# LVDS_IFC_DAC.net
KiCad netlist of a schematic drawn in Altium Designer
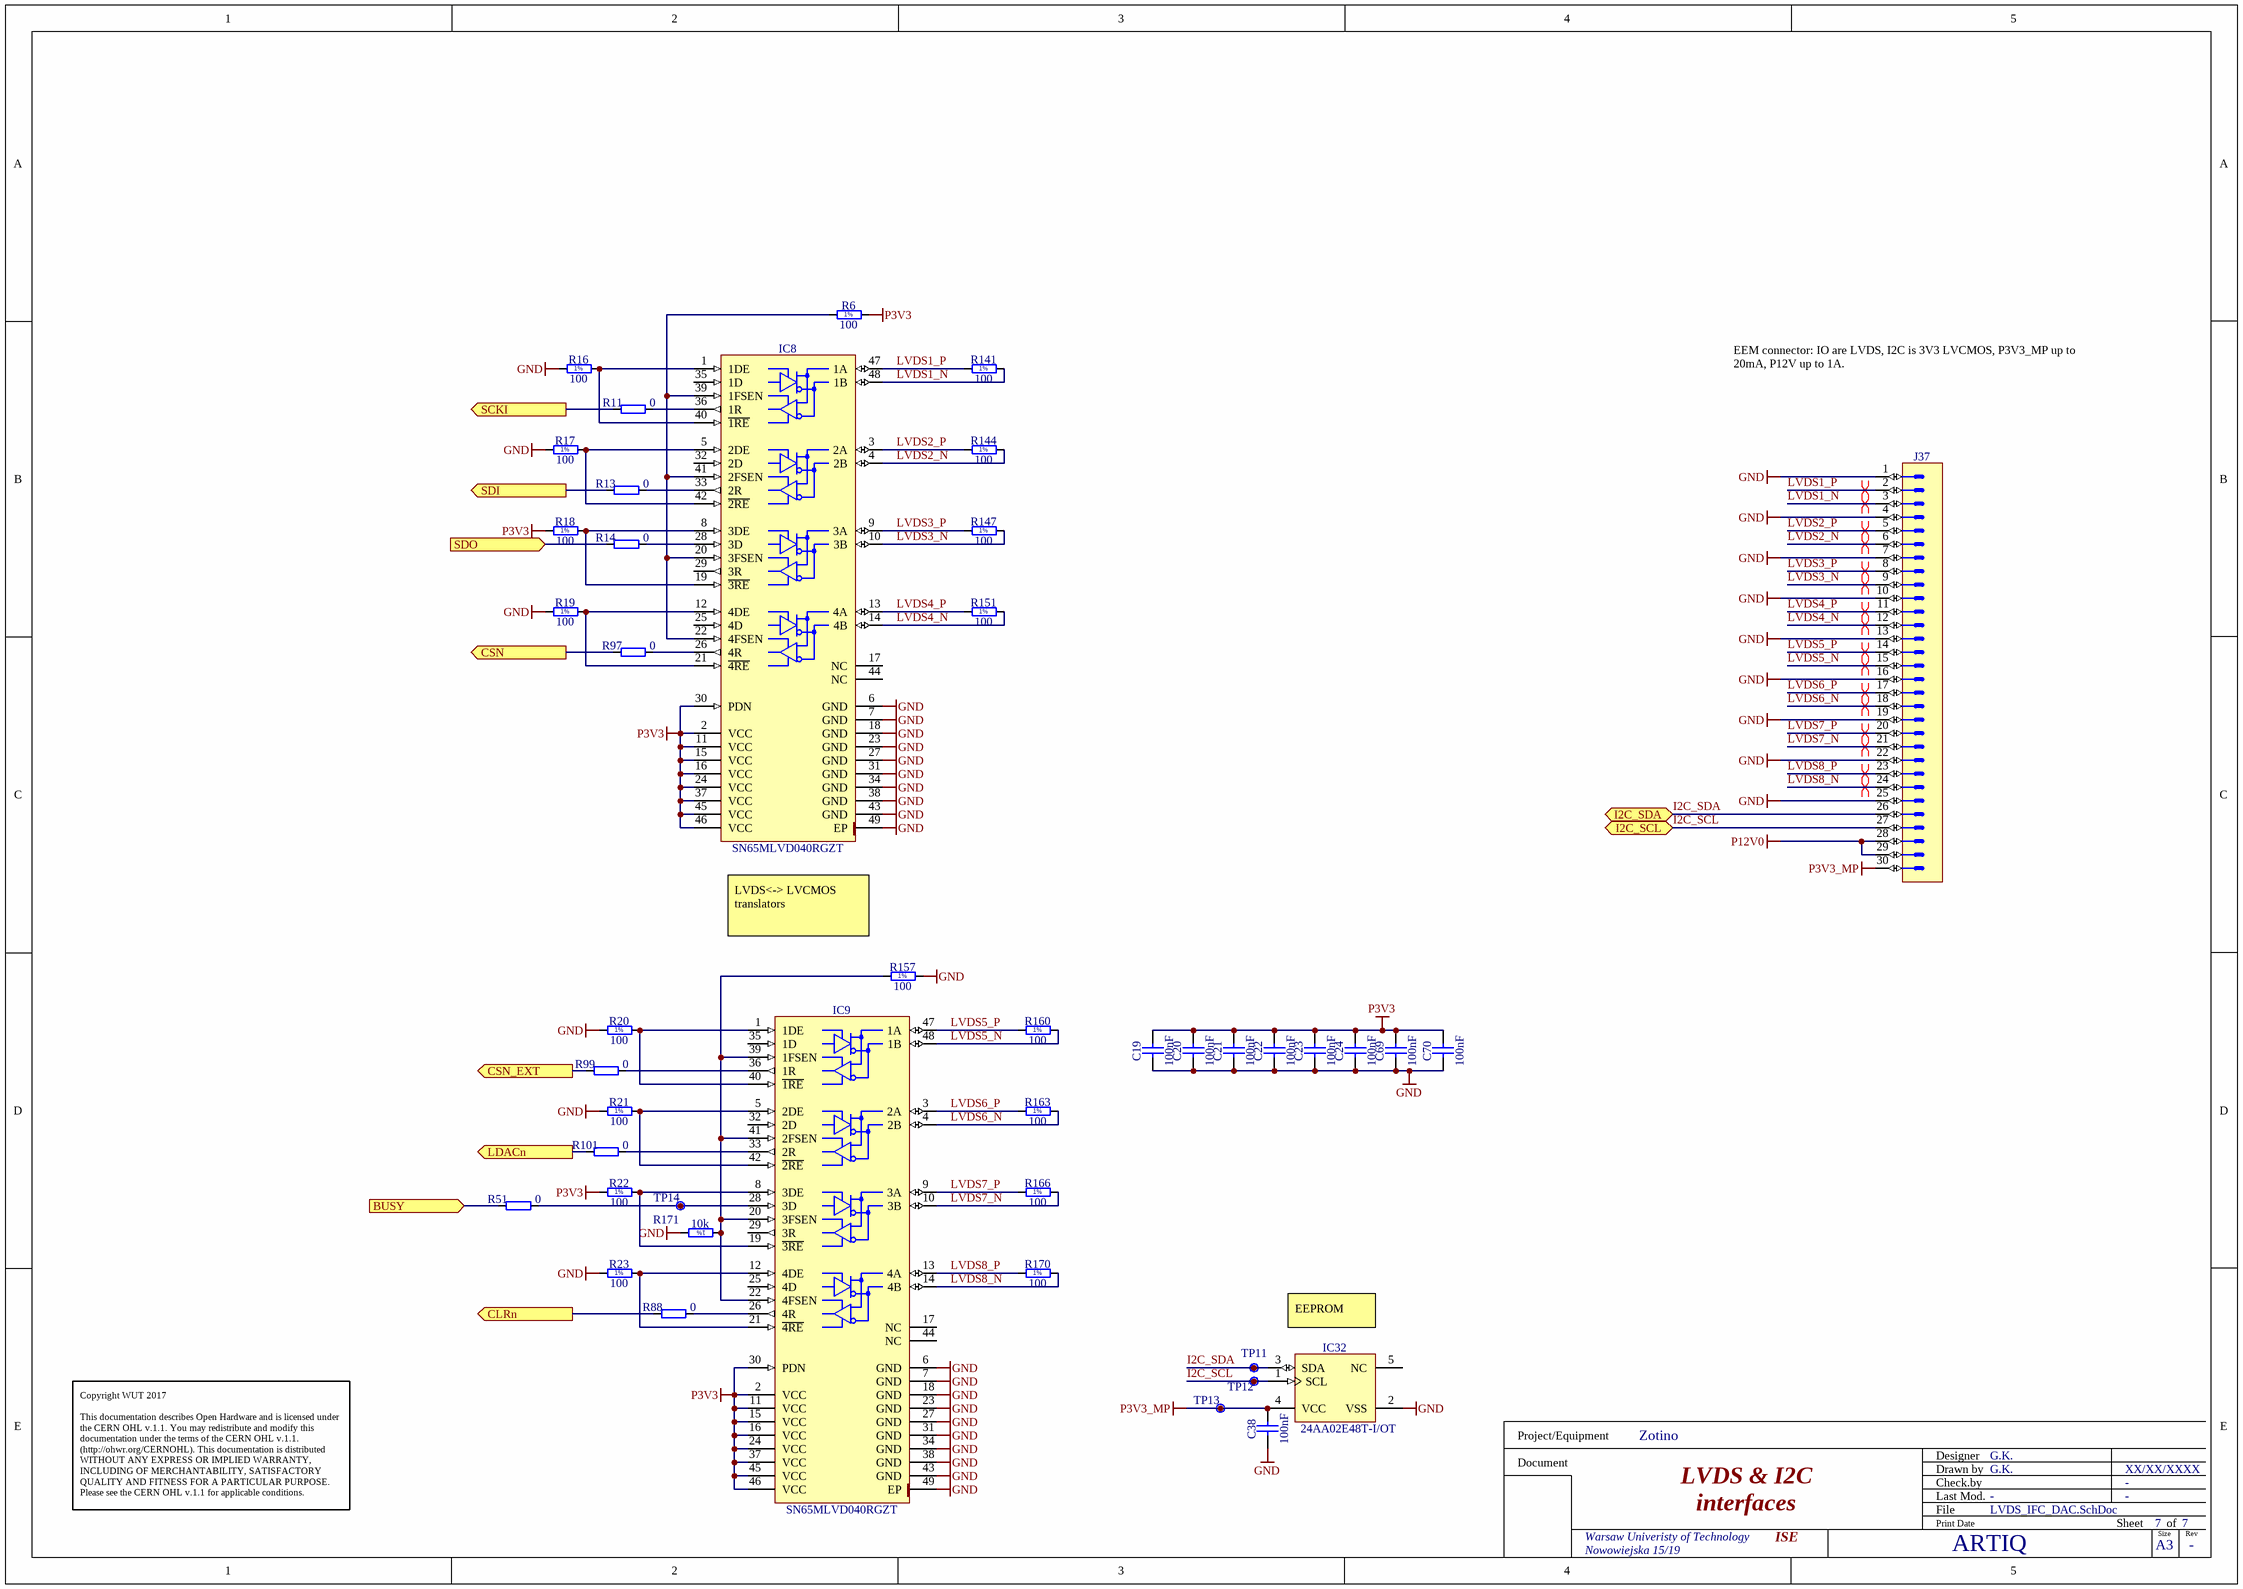
[diagram p0: LVDS_IFC_DAC.SchDoc]

(export (version "E")
  (design (tool "Eeschema 10.0.6"))
  (components
    (comp (ref "C19")
      (value "100nF")
      (footprint "CAPC1005X55N")
      (description "Non-polarised capacitor")
      (fields
        (field (name "PART NUMBER") "CC0402_100NF_16V_10%_X5R")
        (field (name "VOLTAGE") "16V")
        (field (name "AUTHOR") "CERN DEM JLC")
      )
      (libsource (lib "Capacitors") (part "Capacitor - non polarized"))
    )
    (comp (ref "C20")
      (value "100nF")
      (footprint "CAPC1005X55N")
      (description "Non-polarised capacitor")
      (fields
        (field (name "PART NUMBER") "CC0402_100NF_16V_10%_X5R")
        (field (name "VOLTAGE") "16V")
        (field (name "AUTHOR") "CERN DEM JLC")
      )
      (libsource (lib "Capacitors") (part "Capacitor - non polarized"))
    )
    (comp (ref "C21")
      (value "100nF")
      (footprint "CAPC1005X55N")
      (description "Non-polarised capacitor")
      (fields
        (field (name "PART NUMBER") "CC0402_100NF_16V_10%_X5R")
        (field (name "VOLTAGE") "16V")
        (field (name "AUTHOR") "CERN DEM JLC")
      )
      (libsource (lib "Capacitors") (part "Capacitor - non polarized"))
    )
    (comp (ref "C22")
      (value "100nF")
      (footprint "CAPC1005X55N")
      (description "Non-polarised capacitor")
      (fields
        (field (name "PART NUMBER") "CC0402_100NF_16V_10%_X5R")
        (field (name "VOLTAGE") "16V")
        (field (name "AUTHOR") "CERN DEM JLC")
      )
      (libsource (lib "Capacitors") (part "Capacitor - non polarized"))
    )
    (comp (ref "C23")
      (value "100nF")
      (footprint "CAPC1005X55N")
      (description "Non-polarised capacitor")
      (fields
        (field (name "PART NUMBER") "CC0402_100NF_16V_10%_X5R")
        (field (name "VOLTAGE") "16V")
        (field (name "AUTHOR") "CERN DEM JLC")
      )
      (libsource (lib "Capacitors") (part "Capacitor - non polarized"))
    )
    (comp (ref "C24")
      (value "100nF")
      (footprint "CAPC1005X55N")
      (description "Non-polarised capacitor")
      (fields
        (field (name "PART NUMBER") "CC0402_100NF_16V_10%_X5R")
        (field (name "VOLTAGE") "16V")
        (field (name "AUTHOR") "CERN DEM JLC")
      )
      (libsource (lib "Capacitors") (part "Capacitor - non polarized"))
    )
    (comp (ref "C38")
      (value "100nF")
      (footprint "CAPC1005X55N")
      (description "Non-polarised capacitor")
      (fields
        (field (name "PART NUMBER") "CC0402_100NF_16V_10%_X5R")
        (field (name "VOLTAGE") "16V")
        (field (name "AUTHOR") "CERN DEM JLC")
      )
      (libsource (lib "Capacitors") (part "Capacitor - non polarized"))
    )
    (comp (ref "C69")
      (value "100nF")
      (footprint "CAPC1005X55N")
      (description "Non-polarised capacitor")
      (fields
        (field (name "PART NUMBER") "CC0402_100NF_16V_10%_X5R")
        (field (name "VOLTAGE") "16V")
        (field (name "AUTHOR") "CERN DEM JLC")
      )
      (libsource (lib "Capacitors") (part "Capacitor - non polarized"))
    )
    (comp (ref "C70")
      (value "100nF")
      (footprint "CAPC1005X55N")
      (description "Non-polarised capacitor")
      (fields
        (field (name "PART NUMBER") "CC0402_100NF_16V_10%_X5R")
        (field (name "VOLTAGE") "16V")
        (field (name "AUTHOR") "CERN DEM JLC")
      )
      (libsource (lib "Capacitors") (part "Capacitor - non polarized"))
    )
    (comp (ref "IC8")
      (value "SN65MLVD040RGZT")
      (footprint "QFN50P700X700X100-49N-S420")
      (description "4-Channel Half-Duplex M-LVDS Line Transceiver")
      (fields (field (name "MANUFACTURER") "TEXAS INSTRUMENTS") (field (name "AUTHOR") "CERN DEM JLC"))
      (libsource (lib "ICs And Semiconductors") (part "SN65MLVD040"))
    )
    (comp (ref "IC9")
      (value "SN65MLVD040RGZT")
      (footprint "QFN50P700X700X100-49N-S420")
      (description "4-Channel Half-Duplex M-LVDS Line Transceiver")
      (fields (field (name "MANUFACTURER") "TEXAS INSTRUMENTS") (field (name "AUTHOR") "CERN DEM JLC"))
      (libsource (lib "ICs And Semiconductors") (part "SN65MLVD040"))
    )
    (comp (ref "IC32")
      (value "24AA02E48T-I/OT")
      (footprint "SOT95P280X145-5N")
      (description "1.7V-5.5V, 2K I2C Serial EEPROM With EUI-48 Node Identity")
      (fields (field (name "MANUFACTURER") "MICROCHIP TECHNOLOGY") (field (name "AUTHOR") "CERN DEM MR"))
      (libsource (lib "ICs And Semiconductors") (part "24AA02E48T-I/OT"))
    )
    (comp (ref "J37")
      (value "~")
      (footprint "3M_N2530-6002RB")
      (description "Connector 30 Male")
      (fields
        (field (name "PART NUMBER") "3M_N2530-6002RB")
        (field (name "MANUFACTURER") "3M")
        (field (name "AUTHOR") "CERN DEM JLC")
      )
      (libsource (lib "Connectors") (part "Connector 30 Male"))
    )
    (comp (ref "R6")
      (value "100")
      (footprint "RESC1005X40N")
      (description "Resistor - 1%")
      (fields
        (field (name "PART NUMBER") "R0402_100R_1%_0.1W_100PPM")
        (field (name "POWER") "0.1W")
        (field (name "AUTHOR") "CERN DEM JLC")
      )
      (libsource (lib "Resistors") (part "Resistor - 1%"))
    )
    (comp (ref "R11")
      (value "0")
      (footprint "RESC1005X40N")
      (description "Resistor")
      (fields
        (field (name "PART NUMBER") "R0402_0R_JUMPER")
        (field (name "MANUFACTURER") "GENERIC")
        (field (name "AUTHOR") "CERN DEM JLC")
      )
      (libsource (lib "Resistors") (part "Resistor"))
    )
    (comp (ref "R13")
      (value "0")
      (footprint "RESC1005X40N")
      (description "Resistor")
      (fields
        (field (name "PART NUMBER") "R0402_0R_JUMPER")
        (field (name "MANUFACTURER") "GENERIC")
        (field (name "AUTHOR") "CERN DEM JLC")
      )
      (libsource (lib "Resistors") (part "Resistor"))
    )
    (comp (ref "R14")
      (value "0")
      (footprint "RESC1005X40N")
      (description "Resistor")
      (fields
        (field (name "PART NUMBER") "R0402_0R_JUMPER")
        (field (name "MANUFACTURER") "GENERIC")
        (field (name "AUTHOR") "CERN DEM JLC")
      )
      (libsource (lib "Resistors") (part "Resistor"))
    )
    (comp (ref "R16")
      (value "100")
      (footprint "RESC1005X40N")
      (description "Resistor - 1%")
      (fields
        (field (name "PART NUMBER") "R0402_100R_1%_0.1W_100PPM")
        (field (name "POWER") "0.1W")
        (field (name "AUTHOR") "CERN DEM JLC")
      )
      (libsource (lib "Resistors") (part "Resistor - 1%"))
    )
    (comp (ref "R17")
      (value "100")
      (footprint "RESC1005X40N")
      (description "Resistor - 1%")
      (fields
        (field (name "PART NUMBER") "R0402_100R_1%_0.1W_100PPM")
        (field (name "POWER") "0.1W")
        (field (name "AUTHOR") "CERN DEM JLC")
      )
      (libsource (lib "Resistors") (part "Resistor - 1%"))
    )
    (comp (ref "R18")
      (value "100")
      (footprint "RESC1005X40N")
      (description "Resistor - 1%")
      (fields
        (field (name "PART NUMBER") "R0402_100R_1%_0.1W_100PPM")
        (field (name "POWER") "0.1W")
        (field (name "AUTHOR") "CERN DEM JLC")
      )
      (libsource (lib "Resistors") (part "Resistor - 1%"))
    )
    (comp (ref "R19")
      (value "100")
      (footprint "RESC1005X40N")
      (description "Resistor - 1%")
      (fields
        (field (name "PART NUMBER") "R0402_100R_1%_0.1W_100PPM")
        (field (name "POWER") "0.1W")
        (field (name "AUTHOR") "CERN DEM JLC")
      )
      (libsource (lib "Resistors") (part "Resistor - 1%"))
    )
    (comp (ref "R20")
      (value "100")
      (footprint "RESC1005X40N")
      (description "Resistor - 1%")
      (fields
        (field (name "PART NUMBER") "R0402_100R_1%_0.1W_100PPM")
        (field (name "POWER") "0.1W")
        (field (name "AUTHOR") "CERN DEM JLC")
      )
      (libsource (lib "Resistors") (part "Resistor - 1%"))
    )
    (comp (ref "R21")
      (value "100")
      (footprint "RESC1005X40N")
      (description "Resistor - 1%")
      (fields
        (field (name "PART NUMBER") "R0402_100R_1%_0.1W_100PPM")
        (field (name "POWER") "0.1W")
        (field (name "AUTHOR") "CERN DEM JLC")
      )
      (libsource (lib "Resistors") (part "Resistor - 1%"))
    )
    (comp (ref "R22")
      (value "100")
      (footprint "RESC1005X40N")
      (description "Resistor - 1%")
      (fields
        (field (name "PART NUMBER") "R0402_100R_1%_0.1W_100PPM")
        (field (name "POWER") "0.1W")
        (field (name "AUTHOR") "CERN DEM JLC")
      )
      (libsource (lib "Resistors") (part "Resistor - 1%"))
    )
    (comp (ref "R23")
      (value "100")
      (footprint "RESC1005X40N")
      (description "Resistor - 1%")
      (fields
        (field (name "PART NUMBER") "R0402_100R_1%_0.1W_100PPM")
        (field (name "POWER") "0.1W")
        (field (name "AUTHOR") "CERN DEM JLC")
      )
      (libsource (lib "Resistors") (part "Resistor - 1%"))
    )
    (comp (ref "R51")
      (value "0")
      (footprint "RESC1005X40N")
      (description "Resistor")
      (fields
        (field (name "PART NUMBER") "R0402_0R_JUMPER")
        (field (name "MANUFACTURER") "GENERIC")
        (field (name "AUTHOR") "CERN DEM JLC")
      )
      (libsource (lib "Resistors") (part "Resistor"))
    )
    (comp (ref "R88")
      (value "0")
      (footprint "RESC1005X40N")
      (description "Resistor")
      (fields
        (field (name "PART NUMBER") "R0402_0R_JUMPER")
        (field (name "MANUFACTURER") "GENERIC")
        (field (name "AUTHOR") "CERN DEM JLC")
      )
      (libsource (lib "Resistors") (part "Resistor"))
    )
    (comp (ref "R97")
      (value "0")
      (footprint "RESC1005X40N")
      (description "Resistor")
      (fields
        (field (name "PART NUMBER") "R0402_0R_JUMPER")
        (field (name "MANUFACTURER") "GENERIC")
        (field (name "AUTHOR") "CERN DEM JLC")
      )
      (libsource (lib "Resistors") (part "Resistor"))
    )
    (comp (ref "R99")
      (value "0")
      (footprint "RESC1005X40N")
      (description "Resistor")
      (fields
        (field (name "PART NUMBER") "R0402_0R_JUMPER")
        (field (name "MANUFACTURER") "GENERIC")
        (field (name "AUTHOR") "CERN DEM JLC")
      )
      (libsource (lib "Resistors") (part "Resistor"))
    )
    (comp (ref "R101")
      (value "0")
      (footprint "RESC1005X40N")
      (description "Resistor")
      (fields
        (field (name "PART NUMBER") "R0402_0R_JUMPER")
        (field (name "MANUFACTURER") "GENERIC")
        (field (name "AUTHOR") "CERN DEM JLC")
      )
      (libsource (lib "Resistors") (part "Resistor"))
    )
    (comp (ref "R141")
      (value "100")
      (footprint "RESC1005X40N")
      (description "Resistor - 1%")
      (fields
        (field (name "PART NUMBER") "R0402_100R_1%_0.1W_100PPM")
        (field (name "POWER") "0.1W")
        (field (name "AUTHOR") "CERN DEM JLC")
      )
      (libsource (lib "Resistors") (part "Resistor - 1%"))
    )
    (comp (ref "R144")
      (value "100")
      (footprint "RESC1005X40N")
      (description "Resistor - 1%")
      (fields
        (field (name "PART NUMBER") "R0402_100R_1%_0.1W_100PPM")
        (field (name "POWER") "0.1W")
        (field (name "AUTHOR") "CERN DEM JLC")
      )
      (libsource (lib "Resistors") (part "Resistor - 1%"))
    )
    (comp (ref "R147")
      (value "100")
      (footprint "RESC1005X40N")
      (description "Resistor - 1%")
      (fields
        (field (name "PART NUMBER") "R0402_100R_1%_0.1W_100PPM")
        (field (name "POWER") "0.1W")
        (field (name "AUTHOR") "CERN DEM JLC")
      )
      (libsource (lib "Resistors") (part "Resistor - 1%"))
    )
    (comp (ref "R151")
      (value "100")
      (footprint "RESC1005X40N")
      (description "Resistor - 1%")
      (fields
        (field (name "PART NUMBER") "R0402_100R_1%_0.1W_100PPM")
        (field (name "POWER") "0.1W")
        (field (name "AUTHOR") "CERN DEM JLC")
      )
      (libsource (lib "Resistors") (part "Resistor - 1%"))
    )
    (comp (ref "R157")
      (value "100")
      (footprint "RESC1005X40N")
      (description "Resistor - 1%")
      (fields
        (field (name "PART NUMBER") "R0402_100R_1%_0.1W_100PPM")
        (field (name "POWER") "0.1W")
        (field (name "AUTHOR") "CERN DEM JLC")
      )
      (libsource (lib "Resistors") (part "Resistor - 1%"))
    )
    (comp (ref "R160")
      (value "100")
      (footprint "RESC1005X40N")
      (description "Resistor - 1%")
      (fields
        (field (name "PART NUMBER") "R0402_100R_1%_0.1W_100PPM")
        (field (name "POWER") "0.1W")
        (field (name "AUTHOR") "CERN DEM JLC")
      )
      (libsource (lib "Resistors") (part "Resistor - 1%"))
    )
    (comp (ref "R163")
      (value "100")
      (footprint "RESC1005X40N")
      (description "Resistor - 1%")
      (fields
        (field (name "PART NUMBER") "R0402_100R_1%_0.1W_100PPM")
        (field (name "POWER") "0.1W")
        (field (name "AUTHOR") "CERN DEM JLC")
      )
      (libsource (lib "Resistors") (part "Resistor - 1%"))
    )
    (comp (ref "R166")
      (value "100")
      (footprint "RESC1005X40N")
      (description "Resistor - 1%")
      (fields
        (field (name "PART NUMBER") "R0402_100R_1%_0.1W_100PPM")
        (field (name "POWER") "0.1W")
        (field (name "AUTHOR") "CERN DEM JLC")
      )
      (libsource (lib "Resistors") (part "Resistor - 1%"))
    )
    (comp (ref "R170")
      (value "100")
      (footprint "RESC1005X40N")
      (description "Resistor - 1%")
      (fields
        (field (name "PART NUMBER") "R0402_100R_1%_0.1W_100PPM")
        (field (name "POWER") "0.1W")
        (field (name "AUTHOR") "CERN DEM JLC")
      )
      (libsource (lib "Resistors") (part "Resistor - 1%"))
    )
    (comp (ref "R171")
      (value "10k")
      (footprint "RESC1005X40N")
      (description "Resistor - 1%")
      (fields
        (field (name "PART NUMBER") "R0402_10K_1%_0.0625W_100PPM")
        (field (name "POWER") "0.0625W")
        (field (name "AUTHOR") "CERN DEM JLC")
      )
      (libsource (lib "Resistors") (part "Resistor - 1%"))
    )
    (comp (ref "TP11")
      (value "Test Point")
      (footprint "TPS127")
      (fields (field (name "PART NUMBER") "SMD_PAD_1.27X1.27MM") (field (name "AUTHOR") "CERN DEM JLC"))
      (libsource (lib "Eletro-mechanical") (part "Test Point"))
    )
    (comp (ref "TP12")
      (value "Test Point")
      (footprint "TPS127")
      (fields (field (name "PART NUMBER") "SMD_PAD_1.27X1.27MM") (field (name "AUTHOR") "CERN DEM JLC"))
      (libsource (lib "Eletro-mechanical") (part "Test Point"))
    )
    (comp (ref "TP13")
      (value "Test Point")
      (footprint "TPS127")
      (fields (field (name "PART NUMBER") "SMD_PAD_1.27X1.27MM") (field (name "AUTHOR") "CERN DEM JLC"))
      (libsource (lib "Eletro-mechanical") (part "Test Point"))
    )
    (comp (ref "TP14")
      (value "Test Point")
      (footprint "TPS127")
      (fields (field (name "PART NUMBER") "SMD_PAD_1.27X1.27MM") (field (name "AUTHOR") "CERN DEM JLC"))
      (libsource (lib "Eletro-mechanical") (part "Test Point"))
    )
  )
  (nets
    (net (code "1") (name "/BUSY") (class "Default")
      (node (ref "R51") (pin "1") (pinfunction "1_1") (pintype "passive"))
    )
    (net (code "2") (name "/CLRn") (class "Default")
      (node (ref "R88") (pin "1") (pinfunction "1_1") (pintype "passive"))
    )
    (net (code "3") (name "/CSN") (class "Default")
      (node (ref "R97") (pin "1") (pinfunction "1_1") (pintype "passive"))
    )
    (net (code "4") (name "/CSN_EXT") (class "Default")
      (node (ref "R99") (pin "1") (pinfunction "1_1") (pintype "passive"))
    )
    (net (code "5") (name "/I2C_SCL") (class "Default")
      (node (ref "IC32") (pin "1") (pinfunction "SCL_1") (pintype "input"))
      (node (ref "J37") (pin "27") (pinfunction "27_27") (pintype "bidirectional"))
      (node (ref "TP12") (pin "1") (pinfunction "1_1") (pintype "bidirectional"))
    )
    (net (code "6") (name "/I2C_SDA") (class "Default")
      (node (ref "IC32") (pin "3") (pinfunction "SDA_3") (pintype "bidirectional"))
      (node (ref "J37") (pin "26") (pinfunction "26_26") (pintype "bidirectional"))
      (node (ref "TP11") (pin "1") (pinfunction "1_1") (pintype "bidirectional"))
    )
    (net (code "7") (name "/LDACn") (class "Default")
      (node (ref "R101") (pin "1") (pinfunction "1_1") (pintype "passive"))
    )
    (net (code "8") (name "/LVDS1_N") (class "Default")
      (node (ref "IC8") (pin "48") (pinfunction "1B_48") (pintype "bidirectional"))
      (node (ref "J37") (pin "3") (pinfunction "3_3") (pintype "bidirectional"))
      (node (ref "R141") (pin "2") (pinfunction "2_2") (pintype "passive"))
    )
    (net (code "9") (name "/LVDS1_P") (class "Default")
      (node (ref "IC8") (pin "47") (pinfunction "1A_47") (pintype "bidirectional"))
      (node (ref "J37") (pin "2") (pinfunction "2_2") (pintype "bidirectional"))
      (node (ref "R141") (pin "1") (pinfunction "1_1") (pintype "passive"))
    )
    (net (code "10") (name "/LVDS2_N") (class "Default")
      (node (ref "IC8") (pin "4") (pinfunction "2B_4") (pintype "bidirectional"))
      (node (ref "J37") (pin "6") (pinfunction "6_6") (pintype "bidirectional"))
      (node (ref "R144") (pin "2") (pinfunction "2_2") (pintype "passive"))
    )
    (net (code "11") (name "/LVDS2_P") (class "Default")
      (node (ref "IC8") (pin "3") (pinfunction "2A_3") (pintype "bidirectional"))
      (node (ref "J37") (pin "5") (pinfunction "5_5") (pintype "bidirectional"))
      (node (ref "R144") (pin "1") (pinfunction "1_1") (pintype "passive"))
    )
    (net (code "12") (name "/LVDS3_N") (class "Default")
      (node (ref "IC8") (pin "10") (pinfunction "3B_10") (pintype "bidirectional"))
      (node (ref "J37") (pin "9") (pinfunction "9_9") (pintype "bidirectional"))
      (node (ref "R147") (pin "2") (pinfunction "2_2") (pintype "passive"))
    )
    (net (code "13") (name "/LVDS3_P") (class "Default")
      (node (ref "IC8") (pin "9") (pinfunction "3A_9") (pintype "bidirectional"))
      (node (ref "J37") (pin "8") (pinfunction "8_8") (pintype "bidirectional"))
      (node (ref "R147") (pin "1") (pinfunction "1_1") (pintype "passive"))
    )
    (net (code "14") (name "/LVDS4_N") (class "Default")
      (node (ref "IC8") (pin "14") (pinfunction "4B_14") (pintype "bidirectional"))
      (node (ref "J37") (pin "12") (pinfunction "12_12") (pintype "bidirectional"))
      (node (ref "R151") (pin "2") (pinfunction "2_2") (pintype "passive"))
    )
    (net (code "15") (name "/LVDS4_P") (class "Default")
      (node (ref "IC8") (pin "13") (pinfunction "4A_13") (pintype "bidirectional"))
      (node (ref "J37") (pin "11") (pinfunction "11_11") (pintype "bidirectional"))
      (node (ref "R151") (pin "1") (pinfunction "1_1") (pintype "passive"))
    )
    (net (code "16") (name "/LVDS5_N") (class "Default")
      (node (ref "IC9") (pin "48") (pinfunction "1B_48") (pintype "bidirectional"))
      (node (ref "J37") (pin "15") (pinfunction "15_15") (pintype "bidirectional"))
      (node (ref "R160") (pin "2") (pinfunction "2_2") (pintype "passive"))
    )
    (net (code "17") (name "/LVDS5_P") (class "Default")
      (node (ref "IC9") (pin "47") (pinfunction "1A_47") (pintype "bidirectional"))
      (node (ref "J37") (pin "14") (pinfunction "14_14") (pintype "bidirectional"))
      (node (ref "R160") (pin "1") (pinfunction "1_1") (pintype "passive"))
    )
    (net (code "18") (name "/LVDS6_N") (class "Default")
      (node (ref "IC9") (pin "4") (pinfunction "2B_4") (pintype "bidirectional"))
      (node (ref "J37") (pin "18") (pinfunction "18_18") (pintype "bidirectional"))
      (node (ref "R163") (pin "2") (pinfunction "2_2") (pintype "passive"))
    )
    (net (code "19") (name "/LVDS6_P") (class "Default")
      (node (ref "IC9") (pin "3") (pinfunction "2A_3") (pintype "bidirectional"))
      (node (ref "J37") (pin "17") (pinfunction "17_17") (pintype "bidirectional"))
      (node (ref "R163") (pin "1") (pinfunction "1_1") (pintype "passive"))
    )
    (net (code "20") (name "/LVDS7_N") (class "Default")
      (node (ref "IC9") (pin "10") (pinfunction "3B_10") (pintype "bidirectional"))
      (node (ref "J37") (pin "21") (pinfunction "21_21") (pintype "bidirectional"))
      (node (ref "R166") (pin "2") (pinfunction "2_2") (pintype "passive"))
    )
    (net (code "21") (name "/LVDS7_P") (class "Default")
      (node (ref "IC9") (pin "9") (pinfunction "3A_9") (pintype "bidirectional"))
      (node (ref "J37") (pin "20") (pinfunction "20_20") (pintype "bidirectional"))
      (node (ref "R166") (pin "1") (pinfunction "1_1") (pintype "passive"))
    )
    (net (code "22") (name "/LVDS8_N") (class "Default")
      (node (ref "IC9") (pin "14") (pinfunction "4B_14") (pintype "bidirectional"))
      (node (ref "J37") (pin "24") (pinfunction "24_24") (pintype "bidirectional"))
      (node (ref "R170") (pin "2") (pinfunction "2_2") (pintype "passive"))
    )
    (net (code "23") (name "/LVDS8_P") (class "Default")
      (node (ref "IC9") (pin "13") (pinfunction "4A_13") (pintype "bidirectional"))
      (node (ref "J37") (pin "23") (pinfunction "23_23") (pintype "bidirectional"))
      (node (ref "R170") (pin "1") (pinfunction "1_1") (pintype "passive"))
    )
    (net (code "24") (name "/SCKI") (class "Default")
      (node (ref "R11") (pin "1") (pinfunction "1_1") (pintype "passive"))
    )
    (net (code "25") (name "/SDI") (class "Default")
      (node (ref "R13") (pin "1") (pinfunction "1_1") (pintype "passive"))
    )
    (net (code "26") (name "/SDO") (class "Default")
      (node (ref "R14") (pin "1") (pinfunction "1_1") (pintype "passive"))
    )
    (net (code "27") (name "GND") (class "Default")
      (node (ref "C19") (pin "1") (pinfunction "1_1") (pintype "passive"))
      (node (ref "C20") (pin "1") (pinfunction "1_1") (pintype "passive"))
      (node (ref "C21") (pin "1") (pinfunction "1_1") (pintype "passive"))
      (node (ref "C22") (pin "1") (pinfunction "1_1") (pintype "passive"))
      (node (ref "C23") (pin "1") (pinfunction "1_1") (pintype "passive"))
      (node (ref "C24") (pin "1") (pinfunction "1_1") (pintype "passive"))
      (node (ref "C38") (pin "1") (pinfunction "1_1") (pintype "passive"))
      (node (ref "C69") (pin "1") (pinfunction "1_1") (pintype "passive"))
      (node (ref "C70") (pin "1") (pinfunction "1_1") (pintype "passive"))
      (node (ref "IC32") (pin "2") (pinfunction "VSS_2") (pintype "power_in"))
      (node (ref "IC8") (pin "18") (pinfunction "GND_18") (pintype "power_in"))
      (node (ref "IC8") (pin "23") (pinfunction "GND_23") (pintype "power_in"))
      (node (ref "IC8") (pin "27") (pinfunction "GND_27") (pintype "power_in"))
      (node (ref "IC8") (pin "31") (pinfunction "GND_31") (pintype "power_in"))
      (node (ref "IC8") (pin "34") (pinfunction "GND_34") (pintype "power_in"))
      (node (ref "IC8") (pin "38") (pinfunction "GND_38") (pintype "power_in"))
      (node (ref "IC8") (pin "43") (pinfunction "GND_43") (pintype "power_in"))
      (node (ref "IC8") (pin "49") (pinfunction "EP_49") (pintype "power_in"))
      (node (ref "IC8") (pin "6") (pinfunction "GND_6") (pintype "power_in"))
      (node (ref "IC8") (pin "7") (pinfunction "GND_7") (pintype "power_in"))
      (node (ref "IC9") (pin "18") (pinfunction "GND_18") (pintype "power_in"))
      (node (ref "IC9") (pin "23") (pinfunction "GND_23") (pintype "power_in"))
      (node (ref "IC9") (pin "27") (pinfunction "GND_27") (pintype "power_in"))
      (node (ref "IC9") (pin "31") (pinfunction "GND_31") (pintype "power_in"))
      (node (ref "IC9") (pin "34") (pinfunction "GND_34") (pintype "power_in"))
      (node (ref "IC9") (pin "38") (pinfunction "GND_38") (pintype "power_in"))
      (node (ref "IC9") (pin "43") (pinfunction "GND_43") (pintype "power_in"))
      (node (ref "IC9") (pin "49") (pinfunction "EP_49") (pintype "power_in"))
      (node (ref "IC9") (pin "6") (pinfunction "GND_6") (pintype "power_in"))
      (node (ref "IC9") (pin "7") (pinfunction "GND_7") (pintype "power_in"))
      (node (ref "J37") (pin "1") (pinfunction "1_1") (pintype "bidirectional"))
      (node (ref "J37") (pin "10") (pinfunction "10_10") (pintype "bidirectional"))
      (node (ref "J37") (pin "13") (pinfunction "13_13") (pintype "bidirectional"))
      (node (ref "J37") (pin "16") (pinfunction "16_16") (pintype "bidirectional"))
      (node (ref "J37") (pin "19") (pinfunction "19_19") (pintype "bidirectional"))
      (node (ref "J37") (pin "22") (pinfunction "22_22") (pintype "bidirectional"))
      (node (ref "J37") (pin "25") (pinfunction "25_25") (pintype "bidirectional"))
      (node (ref "J37") (pin "4") (pinfunction "4_4") (pintype "bidirectional"))
      (node (ref "J37") (pin "7") (pinfunction "7_7") (pintype "bidirectional"))
      (node (ref "R157") (pin "2") (pinfunction "2_2") (pintype "passive"))
      (node (ref "R16") (pin "1") (pinfunction "1_1") (pintype "passive"))
      (node (ref "R17") (pin "1") (pinfunction "1_1") (pintype "passive"))
      (node (ref "R171") (pin "2") (pinfunction "2_2") (pintype "passive"))
      (node (ref "R19") (pin "1") (pinfunction "1_1") (pintype "passive"))
      (node (ref "R20") (pin "1") (pinfunction "1_1") (pintype "passive"))
      (node (ref "R21") (pin "1") (pinfunction "1_1") (pintype "passive"))
      (node (ref "R23") (pin "1") (pinfunction "1_1") (pintype "passive"))
    )
    (net (code "28") (name "Net-(IC8-1DE)") (class "Default")
      (node (ref "IC8") (pin "1") (pinfunction "1DE_1") (pintype "input"))
      (node (ref "IC8") (pin "40") (pinfunction "~{1RE}_40") (pintype "input"))
      (node (ref "R16") (pin "2") (pinfunction "2_2") (pintype "passive"))
    )
    (net (code "29") (name "Net-(IC8-1FSEN)") (class "Default")
      (node (ref "IC8") (pin "20") (pinfunction "3FSEN_20") (pintype "input"))
      (node (ref "IC8") (pin "22") (pinfunction "4FSEN_22") (pintype "input"))
      (node (ref "IC8") (pin "39") (pinfunction "1FSEN_39") (pintype "input"))
      (node (ref "IC8") (pin "41") (pinfunction "2FSEN_41") (pintype "input"))
      (node (ref "R6") (pin "1") (pinfunction "1_1") (pintype "passive"))
    )
    (net (code "30") (name "Net-(IC8-1R)") (class "Default")
      (node (ref "IC8") (pin "36") (pinfunction "1R_36") (pintype "output"))
      (node (ref "R11") (pin "2") (pinfunction "2_2") (pintype "passive"))
    )
    (net (code "31") (name "Net-(IC8-2DE)") (class "Default")
      (node (ref "IC8") (pin "42") (pinfunction "~{2RE}_42") (pintype "input"))
      (node (ref "IC8") (pin "5") (pinfunction "2DE_5") (pintype "input"))
      (node (ref "R17") (pin "2") (pinfunction "2_2") (pintype "passive"))
    )
    (net (code "32") (name "Net-(IC8-2R)") (class "Default")
      (node (ref "IC8") (pin "33") (pinfunction "2R_33") (pintype "output"))
      (node (ref "R13") (pin "2") (pinfunction "2_2") (pintype "passive"))
    )
    (net (code "33") (name "Net-(IC8-3D)") (class "Default")
      (node (ref "IC8") (pin "28") (pinfunction "3D_28") (pintype "input"))
      (node (ref "R14") (pin "2") (pinfunction "2_2") (pintype "passive"))
    )
    (net (code "34") (name "Net-(IC8-3DE)") (class "Default")
      (node (ref "IC8") (pin "19") (pinfunction "~{3RE}_19") (pintype "input"))
      (node (ref "IC8") (pin "8") (pinfunction "3DE_8") (pintype "input"))
      (node (ref "R18") (pin "2") (pinfunction "2_2") (pintype "passive"))
    )
    (net (code "35") (name "Net-(IC8-4DE)") (class "Default")
      (node (ref "IC8") (pin "12") (pinfunction "4DE_12") (pintype "input"))
      (node (ref "IC8") (pin "21") (pinfunction "~{4RE}_21") (pintype "input"))
      (node (ref "R19") (pin "2") (pinfunction "2_2") (pintype "passive"))
    )
    (net (code "36") (name "Net-(IC8-4R)") (class "Default")
      (node (ref "IC8") (pin "26") (pinfunction "4R_26") (pintype "output"))
      (node (ref "R97") (pin "2") (pinfunction "2_2") (pintype "passive"))
    )
    (net (code "37") (name "Net-(IC9-1DE)") (class "Default")
      (node (ref "IC9") (pin "1") (pinfunction "1DE_1") (pintype "input"))
      (node (ref "IC9") (pin "40") (pinfunction "~{1RE}_40") (pintype "input"))
      (node (ref "R20") (pin "2") (pinfunction "2_2") (pintype "passive"))
    )
    (net (code "38") (name "Net-(IC9-1FSEN)") (class "Default")
      (node (ref "IC9") (pin "20") (pinfunction "3FSEN_20") (pintype "input"))
      (node (ref "IC9") (pin "22") (pinfunction "4FSEN_22") (pintype "input"))
      (node (ref "IC9") (pin "39") (pinfunction "1FSEN_39") (pintype "input"))
      (node (ref "IC9") (pin "41") (pinfunction "2FSEN_41") (pintype "input"))
      (node (ref "R157") (pin "1") (pinfunction "1_1") (pintype "passive"))
      (node (ref "R171") (pin "1") (pinfunction "1_1") (pintype "passive"))
    )
    (net (code "39") (name "Net-(IC9-1R)") (class "Default")
      (node (ref "IC9") (pin "36") (pinfunction "1R_36") (pintype "output"))
      (node (ref "R99") (pin "2") (pinfunction "2_2") (pintype "passive"))
    )
    (net (code "40") (name "Net-(IC9-2DE)") (class "Default")
      (node (ref "IC9") (pin "42") (pinfunction "~{2RE}_42") (pintype "input"))
      (node (ref "IC9") (pin "5") (pinfunction "2DE_5") (pintype "input"))
      (node (ref "R21") (pin "2") (pinfunction "2_2") (pintype "passive"))
    )
    (net (code "41") (name "Net-(IC9-2R)") (class "Default")
      (node (ref "IC9") (pin "33") (pinfunction "2R_33") (pintype "output"))
      (node (ref "R101") (pin "2") (pinfunction "2_2") (pintype "passive"))
    )
    (net (code "42") (name "Net-(IC9-3D)") (class "Default")
      (node (ref "IC9") (pin "28") (pinfunction "3D_28") (pintype "input"))
      (node (ref "R51") (pin "2") (pinfunction "2_2") (pintype "passive"))
      (node (ref "TP14") (pin "1") (pinfunction "1_1") (pintype "bidirectional"))
    )
    (net (code "43") (name "Net-(IC9-3DE)") (class "Default")
      (node (ref "IC9") (pin "19") (pinfunction "~{3RE}_19") (pintype "input"))
      (node (ref "IC9") (pin "8") (pinfunction "3DE_8") (pintype "input"))
      (node (ref "R22") (pin "2") (pinfunction "2_2") (pintype "passive"))
    )
    (net (code "44") (name "Net-(IC9-4DE)") (class "Default")
      (node (ref "IC9") (pin "12") (pinfunction "4DE_12") (pintype "input"))
      (node (ref "IC9") (pin "21") (pinfunction "~{4RE}_21") (pintype "input"))
      (node (ref "R23") (pin "2") (pinfunction "2_2") (pintype "passive"))
    )
    (net (code "45") (name "Net-(IC9-4R)") (class "Default")
      (node (ref "IC9") (pin "26") (pinfunction "4R_26") (pintype "output"))
      (node (ref "R88") (pin "2") (pinfunction "2_2") (pintype "passive"))
    )
    (net (code "46") (name "P3V3") (class "Default")
      (node (ref "C19") (pin "2") (pinfunction "2_2") (pintype "passive"))
      (node (ref "C20") (pin "2") (pinfunction "2_2") (pintype "passive"))
      (node (ref "C21") (pin "2") (pinfunction "2_2") (pintype "passive"))
      (node (ref "C22") (pin "2") (pinfunction "2_2") (pintype "passive"))
      (node (ref "C23") (pin "2") (pinfunction "2_2") (pintype "passive"))
      (node (ref "C24") (pin "2") (pinfunction "2_2") (pintype "passive"))
      (node (ref "C69") (pin "2") (pinfunction "2_2") (pintype "passive"))
      (node (ref "C70") (pin "2") (pinfunction "2_2") (pintype "passive"))
      (node (ref "IC8") (pin "11") (pinfunction "VCC_11") (pintype "power_in"))
      (node (ref "IC8") (pin "15") (pinfunction "VCC_15") (pintype "power_in"))
      (node (ref "IC8") (pin "16") (pinfunction "VCC_16") (pintype "power_in"))
      (node (ref "IC8") (pin "2") (pinfunction "VCC_2") (pintype "power_in"))
      (node (ref "IC8") (pin "24") (pinfunction "VCC_24") (pintype "power_in"))
      (node (ref "IC8") (pin "30") (pinfunction "PDN_30") (pintype "input"))
      (node (ref "IC8") (pin "37") (pinfunction "VCC_37") (pintype "power_in"))
      (node (ref "IC8") (pin "45") (pinfunction "VCC_45") (pintype "power_in"))
      (node (ref "IC8") (pin "46") (pinfunction "VCC_46") (pintype "power_in"))
      (node (ref "IC9") (pin "11") (pinfunction "VCC_11") (pintype "power_in"))
      (node (ref "IC9") (pin "15") (pinfunction "VCC_15") (pintype "power_in"))
      (node (ref "IC9") (pin "16") (pinfunction "VCC_16") (pintype "power_in"))
      (node (ref "IC9") (pin "2") (pinfunction "VCC_2") (pintype "power_in"))
      (node (ref "IC9") (pin "24") (pinfunction "VCC_24") (pintype "power_in"))
      (node (ref "IC9") (pin "30") (pinfunction "PDN_30") (pintype "input"))
      (node (ref "IC9") (pin "37") (pinfunction "VCC_37") (pintype "power_in"))
      (node (ref "IC9") (pin "45") (pinfunction "VCC_45") (pintype "power_in"))
      (node (ref "IC9") (pin "46") (pinfunction "VCC_46") (pintype "power_in"))
      (node (ref "R18") (pin "1") (pinfunction "1_1") (pintype "passive"))
      (node (ref "R22") (pin "1") (pinfunction "1_1") (pintype "passive"))
      (node (ref "R6") (pin "2") (pinfunction "2_2") (pintype "passive"))
    )
    (net (code "47") (name "P3V3_MP") (class "Default")
      (node (ref "C38") (pin "2") (pinfunction "2_2") (pintype "passive"))
      (node (ref "IC32") (pin "4") (pinfunction "VCC_4") (pintype "power_in"))
      (node (ref "J37") (pin "30") (pinfunction "30_30") (pintype "bidirectional"))
      (node (ref "TP13") (pin "1") (pinfunction "1_1") (pintype "bidirectional"))
    )
    (net (code "48") (name "P12V0") (class "Default")
      (node (ref "J37") (pin "28") (pinfunction "28_28") (pintype "bidirectional"))
      (node (ref "J37") (pin "29") (pinfunction "29_29") (pintype "bidirectional"))
    )
    (net (code "49") (name "unconnected-(IC8-1D-Pad35)") (class "Default")
      (node (ref "IC8") (pin "35") (pinfunction "1D_35") (pintype "input"))
    )
    (net (code "50") (name "unconnected-(IC8-2D-Pad32)") (class "Default")
      (node (ref "IC8") (pin "32") (pinfunction "2D_32") (pintype "input"))
    )
    (net (code "51") (name "unconnected-(IC8-3R-Pad29)") (class "Default")
      (node (ref "IC8") (pin "29") (pinfunction "3R_29") (pintype "output"))
    )
    (net (code "52") (name "unconnected-(IC8-4D-Pad25)") (class "Default")
      (node (ref "IC8") (pin "25") (pinfunction "4D_25") (pintype "input"))
    )
    (net (code "53") (name "unconnected-(IC8-NC-Pad17)") (class "Default")
      (node (ref "IC8") (pin "17") (pinfunction "NC_17") (pintype "passive"))
    )
    (net (code "54") (name "unconnected-(IC8-NC-Pad44)") (class "Default")
      (node (ref "IC8") (pin "44") (pinfunction "NC_44") (pintype "passive"))
    )
    (net (code "55") (name "unconnected-(IC9-1D-Pad35)") (class "Default")
      (node (ref "IC9") (pin "35") (pinfunction "1D_35") (pintype "input"))
    )
    (net (code "56") (name "unconnected-(IC9-2D-Pad32)") (class "Default")
      (node (ref "IC9") (pin "32") (pinfunction "2D_32") (pintype "input"))
    )
    (net (code "57") (name "unconnected-(IC9-3R-Pad29)") (class "Default")
      (node (ref "IC9") (pin "29") (pinfunction "3R_29") (pintype "output"))
    )
    (net (code "58") (name "unconnected-(IC9-4D-Pad25)") (class "Default")
      (node (ref "IC9") (pin "25") (pinfunction "4D_25") (pintype "input"))
    )
    (net (code "59") (name "unconnected-(IC9-NC-Pad17)") (class "Default")
      (node (ref "IC9") (pin "17") (pinfunction "NC_17") (pintype "passive"))
    )
    (net (code "60") (name "unconnected-(IC9-NC-Pad44)") (class "Default")
      (node (ref "IC9") (pin "44") (pinfunction "NC_44") (pintype "passive"))
    )
    (net (code "61") (name "unconnected-(IC32-NC-Pad5)") (class "Default")
      (node (ref "IC32") (pin "5") (pinfunction "NC_5") (pintype "passive"))
    )
  )
)
